# Joysticks_connection_unit.net
KiCad netlist of a schematic drawn in EAGLE
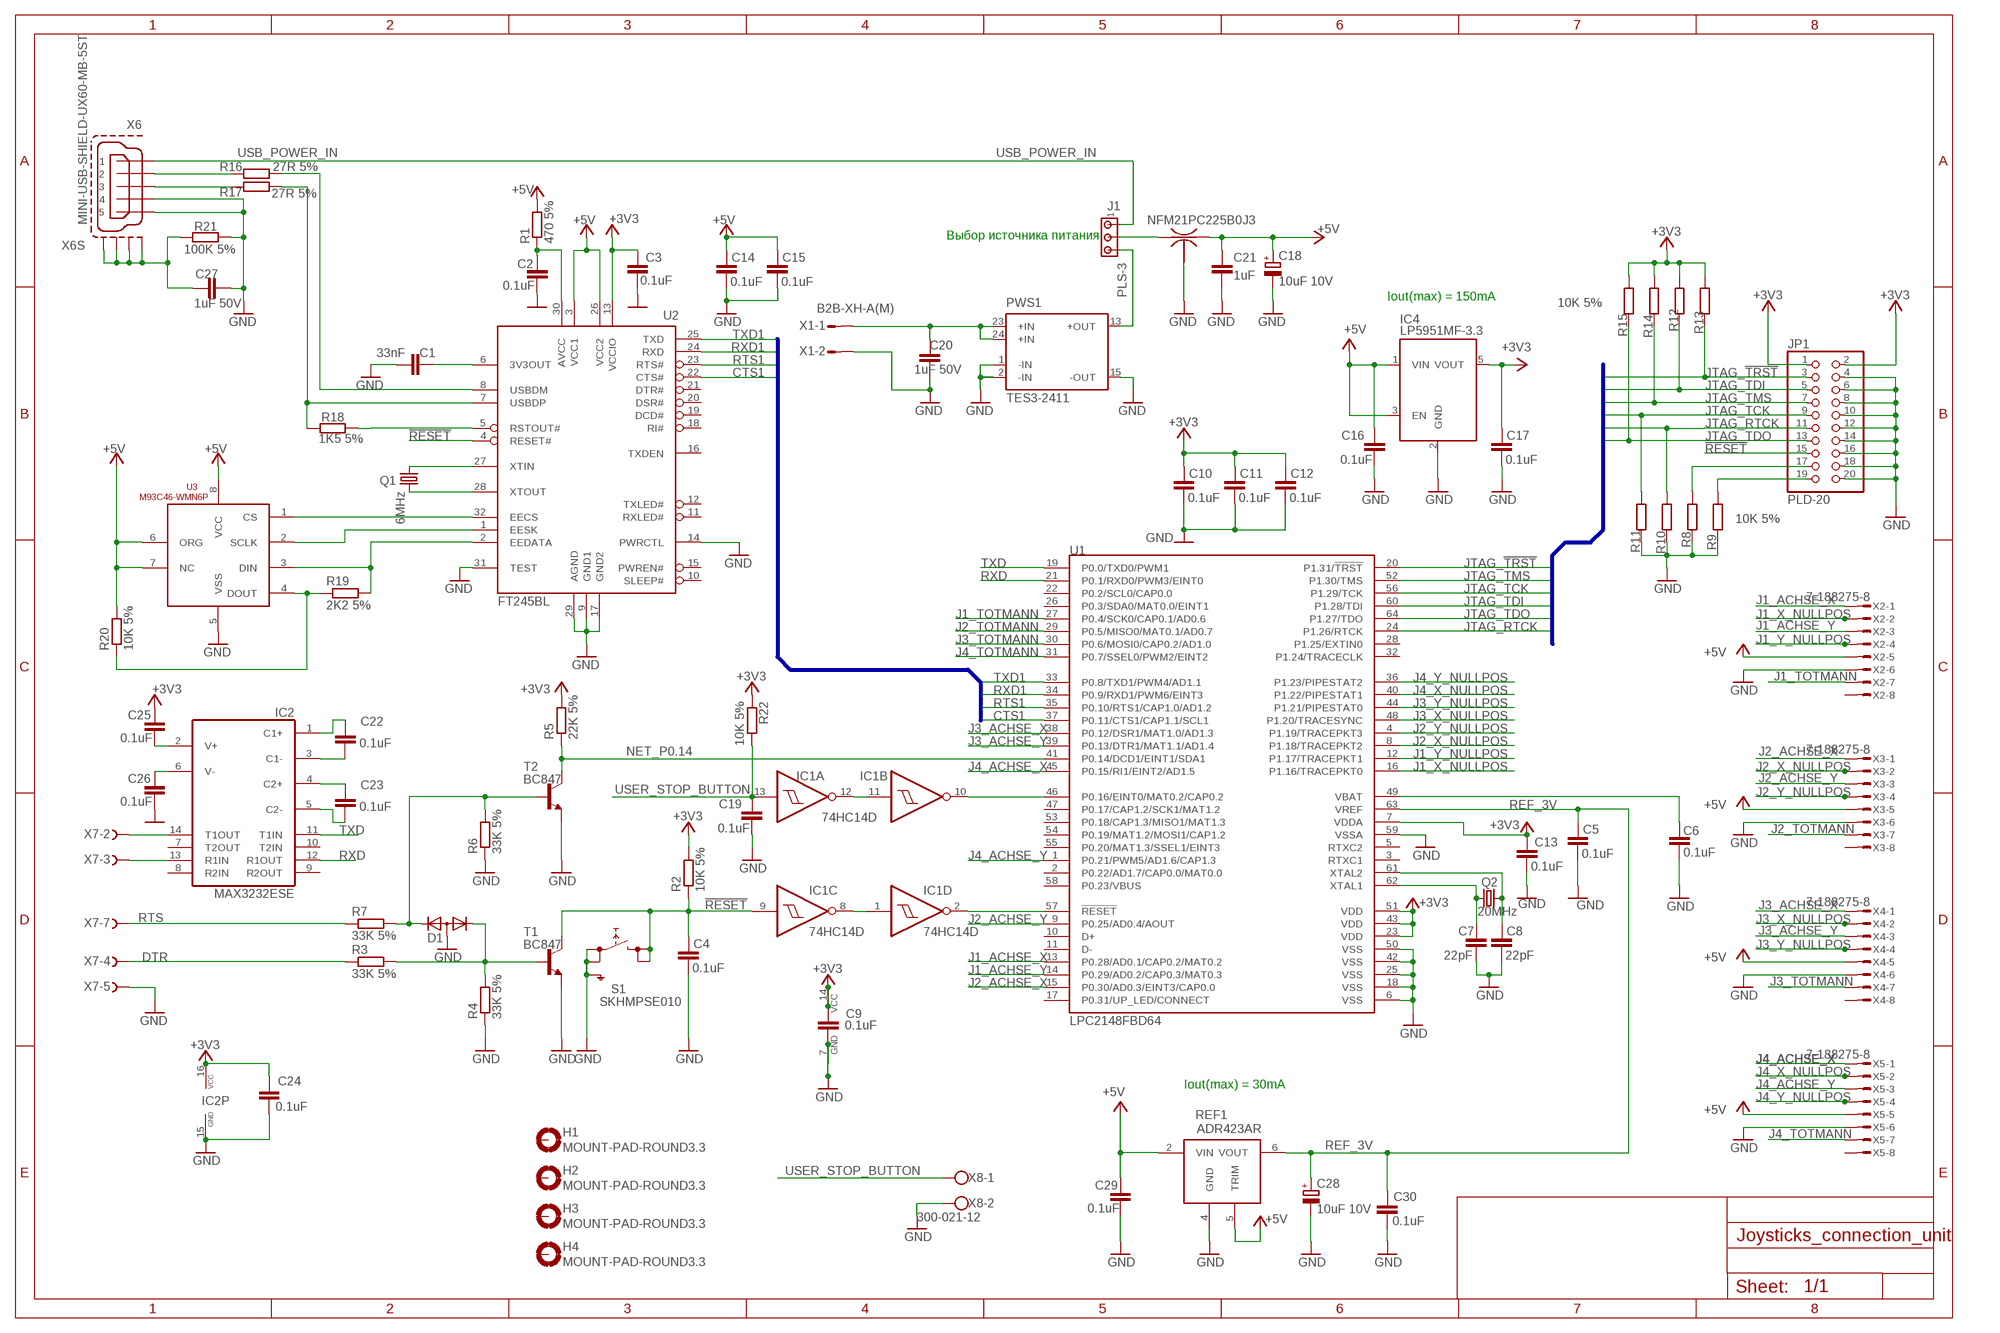
[diagram p0: schematic, sheet 1]

(export (version "E")
  (design (tool "Eeschema 10.0.6"))
  (components
    (comp (ref "C1")
      (value "33nF")
      (footprint "eagle-import:C0805")
      (libsource (lib "eagle-import") (part "C-EUC0805"))
    )
    (comp (ref "C2")
      (value "0.1uF")
      (footprint "eagle-import:C0805")
      (libsource (lib "eagle-import") (part "C-EUC0805"))
    )
    (comp (ref "C3")
      (value "0.1uF")
      (footprint "eagle-import:C0805")
      (libsource (lib "eagle-import") (part "C-EUC0805"))
    )
    (comp (ref "C4")
      (value "0.1uF")
      (footprint "eagle-import:C0805")
      (libsource (lib "eagle-import") (part "C-EUC0805"))
    )
    (comp (ref "C5")
      (value "0.1uF")
      (footprint "eagle-import:C0805")
      (libsource (lib "eagle-import") (part "C-EUC0805"))
    )
    (comp (ref "C6")
      (value "0.1uF")
      (footprint "eagle-import:C0805")
      (libsource (lib "eagle-import") (part "C-EUC0805"))
    )
    (comp (ref "C7")
      (value "22pF")
      (footprint "eagle-import:C0805")
      (libsource (lib "eagle-import") (part "C-EUC0805"))
    )
    (comp (ref "C8")
      (value "22pF")
      (footprint "eagle-import:C0805")
      (libsource (lib "eagle-import") (part "C-EUC0805"))
    )
    (comp (ref "C9")
      (value "0.1uF")
      (footprint "eagle-import:C0805")
      (libsource (lib "eagle-import") (part "C-EUC0805"))
    )
    (comp (ref "C10")
      (value "0.1uF")
      (footprint "eagle-import:C0805")
      (libsource (lib "eagle-import") (part "C-EUC0805"))
    )
    (comp (ref "C11")
      (value "0.1uF")
      (footprint "eagle-import:C0805")
      (libsource (lib "eagle-import") (part "C-EUC0805"))
    )
    (comp (ref "C12")
      (value "0.1uF")
      (footprint "eagle-import:C0805")
      (libsource (lib "eagle-import") (part "C-EUC0805"))
    )
    (comp (ref "C13")
      (value "0.1uF")
      (footprint "eagle-import:C0805")
      (libsource (lib "eagle-import") (part "C-EUC0805"))
    )
    (comp (ref "C14")
      (value "0.1uF")
      (footprint "eagle-import:C0805")
      (libsource (lib "eagle-import") (part "C-EUC0805"))
    )
    (comp (ref "C15")
      (value "0.1uF")
      (footprint "eagle-import:C0805")
      (libsource (lib "eagle-import") (part "C-EUC0805"))
    )
    (comp (ref "C16")
      (value "0.1uF")
      (footprint "eagle-import:C0805")
      (libsource (lib "eagle-import") (part "C-EUC0805"))
    )
    (comp (ref "C17")
      (value "0.1uF")
      (footprint "eagle-import:C0805")
      (libsource (lib "eagle-import") (part "C-EUC0805"))
    )
    (comp (ref "C18")
      (value "10uF 10V")
      (footprint "eagle-import:SMC_B")
      (libsource (lib "eagle-import") (part "CPOL-EUSMCB"))
    )
    (comp (ref "C19")
      (value "0.1uF")
      (footprint "eagle-import:C0805")
      (libsource (lib "eagle-import") (part "C-EUC0805"))
    )
    (comp (ref "C20")
      (value "1uF 50V")
      (footprint "eagle-import:C0805")
      (libsource (lib "eagle-import") (part "C-EUC0805"))
    )
    (comp (ref "C21")
      (value "1uF")
      (footprint "eagle-import:C0805")
      (libsource (lib "eagle-import") (part "C-EUC0805"))
    )
    (comp (ref "C22")
      (value "0.1uF")
      (footprint "eagle-import:C0805")
      (libsource (lib "eagle-import") (part "C-EUC0805"))
    )
    (comp (ref "C23")
      (value "0.1uF")
      (footprint "eagle-import:C0805")
      (libsource (lib "eagle-import") (part "C-EUC0805"))
    )
    (comp (ref "C24")
      (value "0.1uF")
      (footprint "eagle-import:C0805")
      (libsource (lib "eagle-import") (part "C-EUC0805"))
    )
    (comp (ref "C25")
      (value "0.1uF")
      (footprint "eagle-import:C0805")
      (libsource (lib "eagle-import") (part "C-EUC0805"))
    )
    (comp (ref "C26")
      (value "0.1uF")
      (footprint "eagle-import:C0805")
      (libsource (lib "eagle-import") (part "C-EUC0805"))
    )
    (comp (ref "C27")
      (value "1uF 50V")
      (footprint "eagle-import:C0805")
      (libsource (lib "eagle-import") (part "C-EUC0805"))
    )
    (comp (ref "C28")
      (value "10uF 10V")
      (footprint "eagle-import:SMC_B")
      (libsource (lib "eagle-import") (part "CPOL-EUSMCB"))
    )
    (comp (ref "C29")
      (value "0.1uF")
      (footprint "eagle-import:C0805")
      (libsource (lib "eagle-import") (part "C-EUC0805"))
    )
    (comp (ref "C30")
      (value "0.1uF")
      (footprint "eagle-import:C0805")
      (libsource (lib "eagle-import") (part "C-EUC0805"))
    )
    (comp (ref "CF1")
      (value "NFM21PC225B0J3")
      (footprint "eagle-import:NFM21C")
      (fields (field (name "MPN") "NFM21CC102R1H3D"))
      (libsource (lib "eagle-import") (part "NFM21C"))
    )
    (comp (ref "D1")
      (value "DIODE-2CA|ACSOT23")
      (footprint "eagle-import:SOT23")
      (libsource (lib "eagle-import") (part "DIODE-2CA|ACSOT23"))
    )
    (comp (ref "H1")
      (value "MOUNT-PAD-ROUND3.3")
      (footprint "eagle-import:3,3-PAD")
      (libsource (lib "eagle-import") (part "MOUNT-PAD-ROUND3.3"))
    )
    (comp (ref "H2")
      (value "MOUNT-PAD-ROUND3.3")
      (footprint "eagle-import:3,3-PAD")
      (libsource (lib "eagle-import") (part "MOUNT-PAD-ROUND3.3"))
    )
    (comp (ref "H3")
      (value "MOUNT-PAD-ROUND3.3")
      (footprint "eagle-import:3,3-PAD")
      (libsource (lib "eagle-import") (part "MOUNT-PAD-ROUND3.3"))
    )
    (comp (ref "H4")
      (value "MOUNT-PAD-ROUND3.3")
      (footprint "eagle-import:3,3-PAD")
      (libsource (lib "eagle-import") (part "MOUNT-PAD-ROUND3.3"))
    )
    (comp (ref "IC1")
      (value "74HC14D")
      (footprint "eagle-import:SO14")
      (libsource (lib "eagle-import") (part "7414DHC"))
    )
    (comp (ref "IC2")
      (value "MAX3232ESE")
      (footprint "eagle-import:SO16")
      (fields (field (name "MF") "MAXIM"))
      (libsource (lib "eagle-import") (part "MAX3232SEE"))
    )
    (comp (ref "IC4")
      (value "LP5951MF-3.3")
      (footprint "eagle-import:SOT23-5(MF05A)")
      (libsource (lib "eagle-import") (part "LP5951MF-3.3"))
    )
    (comp (ref "J1")
      (value "PLS-3")
      (footprint "eagle-import:10X03MTA")
      (libsource (lib "eagle-import") (part "MTA03-100"))
    )
    (comp (ref "JP1")
      (value "PLD-20")
      (footprint "eagle-import:2X10")
      (libsource (lib "eagle-import") (part "PINHD-2X10"))
    )
    (comp (ref "PWS1")
      (value "TES3-2411")
      (footprint "eagle-import:TES3")
      (libsource (lib "eagle-import") (part "TES3-2411"))
    )
    (comp (ref "Q1")
      (value "6MHz")
      (footprint "eagle-import:HC49_S")
      (fields (field (name "OC_FARNELL") "1667008") (field (name "OC_NEWARK") "unknown"))
      (libsource (lib "eagle-import") (part "CRYSTALHC49S"))
    )
    (comp (ref "Q2")
      (value "20MHz")
      (footprint "eagle-import:HC49_S")
      (libsource (lib "eagle-import") (part "CRYSTALHC49S"))
    )
    (comp (ref "R1")
      (value "470 5%")
      (footprint "eagle-import:R0805")
      (libsource (lib "eagle-import") (part "R-EU_R0805"))
    )
    (comp (ref "R2")
      (value "10K 5%")
      (footprint "eagle-import:R0805")
      (libsource (lib "eagle-import") (part "R-EU_R0805"))
    )
    (comp (ref "R3")
      (value "33K 5%")
      (footprint "eagle-import:R0805")
      (libsource (lib "eagle-import") (part "R-EU_R0805"))
    )
    (comp (ref "R4")
      (value "33K 5%")
      (footprint "eagle-import:R0805")
      (libsource (lib "eagle-import") (part "R-EU_R0805"))
    )
    (comp (ref "R5")
      (value "22K 5%")
      (footprint "eagle-import:R0805")
      (libsource (lib "eagle-import") (part "R-EU_R0805"))
    )
    (comp (ref "R6")
      (value "33K 5%")
      (footprint "eagle-import:R0805")
      (libsource (lib "eagle-import") (part "R-EU_R0805"))
    )
    (comp (ref "R7")
      (value "33K 5%")
      (footprint "eagle-import:R0805")
      (libsource (lib "eagle-import") (part "R-EU_R0805"))
    )
    (comp (ref "R8")
      (value "10K 5%")
      (footprint "eagle-import:R0805")
      (libsource (lib "eagle-import") (part "R-EU_R0805"))
    )
    (comp (ref "R9")
      (value "10K 5%")
      (footprint "eagle-import:R0805")
      (libsource (lib "eagle-import") (part "R-EU_R0805"))
    )
    (comp (ref "R10")
      (value "10K 5%")
      (footprint "eagle-import:R0805")
      (libsource (lib "eagle-import") (part "R-EU_R0805"))
    )
    (comp (ref "R11")
      (value "10K 5%")
      (footprint "eagle-import:R0805")
      (libsource (lib "eagle-import") (part "R-EU_R0805"))
    )
    (comp (ref "R12")
      (value "10K 5%")
      (footprint "eagle-import:R0805")
      (libsource (lib "eagle-import") (part "R-EU_R0805"))
    )
    (comp (ref "R13")
      (value "10K 5%")
      (footprint "eagle-import:R0805")
      (libsource (lib "eagle-import") (part "R-EU_R0805"))
    )
    (comp (ref "R14")
      (value "10K 5%")
      (footprint "eagle-import:R0805")
      (libsource (lib "eagle-import") (part "R-EU_R0805"))
    )
    (comp (ref "R15")
      (value "10K 5%")
      (footprint "eagle-import:R0805")
      (libsource (lib "eagle-import") (part "R-EU_R0805"))
    )
    (comp (ref "R16")
      (value "27R 5%")
      (footprint "eagle-import:R0805")
      (libsource (lib "eagle-import") (part "R-EU_R0805"))
    )
    (comp (ref "R17")
      (value "27R 5%")
      (footprint "eagle-import:R0805")
      (libsource (lib "eagle-import") (part "R-EU_R0805"))
    )
    (comp (ref "R18")
      (value "1K5 5%")
      (footprint "eagle-import:R0805")
      (libsource (lib "eagle-import") (part "R-EU_R0805"))
    )
    (comp (ref "R19")
      (value "2K2 5%")
      (footprint "eagle-import:R0805")
      (libsource (lib "eagle-import") (part "R-EU_R0805"))
    )
    (comp (ref "R20")
      (value "10K 5%")
      (footprint "eagle-import:R0805")
      (libsource (lib "eagle-import") (part "R-EU_R0805"))
    )
    (comp (ref "R21")
      (value "100K 5%")
      (footprint "eagle-import:R0805")
      (libsource (lib "eagle-import") (part "R-EU_R0805"))
    )
    (comp (ref "R22")
      (value "10K 5%")
      (footprint "eagle-import:R0805")
      (libsource (lib "eagle-import") (part "R-EU_R0805"))
    )
    (comp (ref "REF1")
      (value "ADR423AR")
      (footprint "eagle-import:SOIC8")
      (libsource (lib "eagle-import") (part "ADR423AR"))
    )
    (comp (ref "S1")
      (value "SKHMPSE010")
      (footprint "eagle-import:SKHMPXE010")
      (libsource (lib "eagle-import") (part "SKHMPE010S"))
    )
    (comp (ref "T1")
      (value "BC847")
      (footprint "eagle-import:SOT23")
      (libsource (lib "eagle-import") (part "BC847"))
    )
    (comp (ref "T2")
      (value "BC847")
      (footprint "eagle-import:SOT23")
      (libsource (lib "eagle-import") (part "BC847"))
    )
    (comp (ref "U1")
      (value "LPC2148FBD64")
      (footprint "eagle-import:TSQFP50P1200X1200X160-64N")
      (libsource (lib "eagle-import") (part "LPC2148FBD64"))
    )
    (comp (ref "U2")
      (value "FT245BL")
      (footprint "eagle-import:LQFP32")
      (libsource (lib "eagle-import") (part "FT245BL"))
    )
    (comp (ref "U3")
      (value "M93C46-WMN6P")
      (footprint "eagle-import:SO8")
      (libsource (lib "eagle-import") (part "M93C46-WMN6P"))
    )
    (comp (ref "X1")
      (value "B2B-XH-A(M)")
      (footprint "eagle-import:B2B-XH-AM")
      (libsource (lib "eagle-import") (part "B2B-XH-A(M)"))
    )
    (comp (ref "X2")
      (value "7-188275-8")
      (footprint "eagle-import:MMT-F-SMD-8")
      (libsource (lib "eagle-import") (part "MICROMATCH-8SMF"))
    )
    (comp (ref "X3")
      (value "7-188275-8")
      (footprint "eagle-import:MMT-F-SMD-8")
      (libsource (lib "eagle-import") (part "MICROMATCH-8SMF"))
    )
    (comp (ref "X4")
      (value "7-188275-8")
      (footprint "eagle-import:MMT-F-SMD-8")
      (libsource (lib "eagle-import") (part "MICROMATCH-8SMF"))
    )
    (comp (ref "X5")
      (value "7-188275-8")
      (footprint "eagle-import:MMT-F-SMD-8")
      (libsource (lib "eagle-import") (part "MICROMATCH-8SMF"))
    )
    (comp (ref "X6")
      (value "MINI-USB-SHIELD-UX60-MB-5ST")
      (footprint "eagle-import:UX60-MB-5ST")
      (libsource (lib "eagle-import") (part "MINI-USB-SHIELD-UX60-MB-5ST"))
    )
    (comp (ref "X7")
      (value "F09VPS")
      (footprint "eagle-import:F09VP")
      (libsource (lib "eagle-import") (part "F09?SVP"))
    )
    (comp (ref "X8")
      (value "300-021-12")
      (footprint "eagle-import:W237-102")
      (fields (field (name "MPN") "237-102"))
      (libsource (lib "eagle-import") (part "W237-102"))
    )
  )
  (nets
    (net (code "1") (name "+3V3") (class "Default")
      (node (ref "C10") (pin "1") (pinfunction "1_1") (pintype "passive"))
      (node (ref "C11") (pin "1") (pinfunction "1_1") (pintype "passive"))
      (node (ref "C12") (pin "1") (pinfunction "1_1") (pintype "passive"))
      (node (ref "C13") (pin "1") (pinfunction "1_1") (pintype "passive"))
      (node (ref "C17") (pin "1") (pinfunction "1_1") (pintype "passive"))
      (node (ref "C24") (pin "1") (pinfunction "1_1") (pintype "passive"))
      (node (ref "C25") (pin "1") (pinfunction "1_1") (pintype "passive"))
      (node (ref "C3") (pin "1") (pinfunction "1_1") (pintype "passive"))
      (node (ref "C9") (pin "1") (pinfunction "1_1") (pintype "passive"))
      (node (ref "IC1") (pin "14") (pinfunction "VCC_14") (pintype "power_in"))
      (node (ref "IC2") (pin "16") (pinfunction "VCC_16") (pintype "power_in"))
      (node (ref "IC4") (pin "5") (pinfunction "VOUT_5") (pintype "power_in"))
      (node (ref "JP1") (pin "1") (pinfunction "1_1") (pintype "passive"))
      (node (ref "JP1") (pin "2") (pinfunction "2_2") (pintype "passive"))
      (node (ref "R12") (pin "2") (pinfunction "2_2") (pintype "passive"))
      (node (ref "R13") (pin "2") (pinfunction "2_2") (pintype "passive"))
      (node (ref "R14") (pin "2") (pinfunction "2_2") (pintype "passive"))
      (node (ref "R15") (pin "2") (pinfunction "2_2") (pintype "passive"))
      (node (ref "R2") (pin "2") (pinfunction "2_2") (pintype "passive"))
      (node (ref "R22") (pin "1") (pinfunction "1_1") (pintype "passive"))
      (node (ref "R5") (pin "2") (pinfunction "2_2") (pintype "passive"))
      (node (ref "U1") (pin "23") (pinfunction "VDD_23") (pintype "power_in"))
      (node (ref "U1") (pin "43") (pinfunction "VDD_43") (pintype "power_in"))
      (node (ref "U1") (pin "51") (pinfunction "VDD_51") (pintype "power_in"))
      (node (ref "U1") (pin "7") (pinfunction "VDDA_7") (pintype "power_in"))
      (node (ref "U2") (pin "13") (pinfunction "VCCIO_13") (pintype "power_in"))
    )
    (net (code "2") (name "+5V") (class "Default")
      (node (ref "C14") (pin "1") (pinfunction "1_1") (pintype "passive"))
      (node (ref "C15") (pin "1") (pinfunction "1_1") (pintype "passive"))
      (node (ref "C16") (pin "1") (pinfunction "1_1") (pintype "passive"))
      (node (ref "C18") (pin "+") (pinfunction "+_+") (pintype "passive"))
      (node (ref "C21") (pin "1") (pinfunction "1_1") (pintype "passive"))
      (node (ref "C29") (pin "1") (pinfunction "1_1") (pintype "passive"))
      (node (ref "CF1") (pin "3") (pinfunction "3_3") (pintype "passive"))
      (node (ref "IC4") (pin "1") (pinfunction "VIN_1") (pintype "input"))
      (node (ref "IC4") (pin "3") (pinfunction "EN_3") (pintype "input"))
      (node (ref "R1") (pin "2") (pinfunction "2_2") (pintype "passive"))
      (node (ref "R20") (pin "2") (pinfunction "2_2") (pintype "passive"))
      (node (ref "REF1") (pin "2") (pinfunction "VIN_2") (pintype "input"))
      (node (ref "REF1") (pin "5") (pinfunction "TRIM_5") (pintype "input"))
      (node (ref "U2") (pin "26") (pinfunction "VCC2_26") (pintype "power_in"))
      (node (ref "U2") (pin "3") (pinfunction "VCC1_3") (pintype "power_in"))
      (node (ref "U3") (pin "6") (pinfunction "ORG_6") (pintype "input"))
      (node (ref "U3") (pin "7") (pinfunction "NC_7") (pintype "input"))
      (node (ref "U3") (pin "8") (pinfunction "VCC_8") (pintype "power_in"))
      (node (ref "X2") (pin "5") (pinfunction "S_5") (pintype "passive"))
      (node (ref "X3") (pin "5") (pinfunction "S_5") (pintype "passive"))
      (node (ref "X4") (pin "5") (pinfunction "S_5") (pintype "passive"))
      (node (ref "X5") (pin "5") (pinfunction "S_5") (pintype "passive"))
    )
    (net (code "3") (name "/CTS1") (class "Default")
      (node (ref "U1") (pin "37") (pinfunction "P0.11/CTS1/CAP1.1/SCL1_37") (pintype "bidirectional"))
      (node (ref "U2") (pin "22") (pinfunction "CTS#_22") (pintype "input"))
    )
    (net (code "4") (name "/DTR") (class "Default")
      (node (ref "R3") (pin "1") (pinfunction "1_1") (pintype "passive"))
      (node (ref "X7") (pin "4") (pinfunction "F_4") (pintype "passive"))
    )
    (net (code "5") (name "/J1_ACHSE_X") (class "Default")
      (node (ref "U1") (pin "13") (pinfunction "P0.28/AD0.1/CAP0.2/MAT0.2_13") (pintype "bidirectional"))
      (node (ref "X2") (pin "1") (pinfunction "S_1") (pintype "passive"))
    )
    (net (code "6") (name "/J1_ACHSE_Y") (class "Default")
      (node (ref "U1") (pin "14") (pinfunction "P0.29/AD0.2/CAP0.3/MAT0.3_14") (pintype "bidirectional"))
      (node (ref "X2") (pin "3") (pinfunction "S_3") (pintype "passive"))
    )
    (net (code "7") (name "/J1_TOTMANN") (class "Default")
      (node (ref "U1") (pin "27") (pinfunction "P0.4/SCK0/CAP0.1/AD0.6_27") (pintype "bidirectional"))
      (node (ref "X2") (pin "7") (pinfunction "S_7") (pintype "passive"))
    )
    (net (code "8") (name "/J1_X_NULLPOS") (class "Default")
      (node (ref "U1") (pin "16") (pinfunction "P1.16/TRACEPKT0_16") (pintype "bidirectional"))
      (node (ref "X2") (pin "2") (pinfunction "S_2") (pintype "passive"))
    )
    (net (code "9") (name "/J1_Y_NULLPOS") (class "Default")
      (node (ref "U1") (pin "12") (pinfunction "P1.17/TRACEPKT1_12") (pintype "bidirectional"))
      (node (ref "X2") (pin "4") (pinfunction "S_4") (pintype "passive"))
    )
    (net (code "10") (name "/J2_ACHSE_X") (class "Default")
      (node (ref "U1") (pin "15") (pinfunction "P0.30/AD0.3/EINT3/CAP0.0_15") (pintype "bidirectional"))
      (node (ref "X3") (pin "1") (pinfunction "S_1") (pintype "passive"))
    )
    (net (code "11") (name "/J2_ACHSE_Y") (class "Default")
      (node (ref "U1") (pin "9") (pinfunction "P0.25/AD0.4/AOUT_9") (pintype "bidirectional"))
      (node (ref "X3") (pin "3") (pinfunction "S_3") (pintype "passive"))
    )
    (net (code "12") (name "/J2_TOTMANN") (class "Default")
      (node (ref "U1") (pin "29") (pinfunction "P0.5/MISO0/MAT0.1/AD0.7_29") (pintype "bidirectional"))
      (node (ref "X3") (pin "7") (pinfunction "S_7") (pintype "passive"))
    )
    (net (code "13") (name "/J2_X_NULLPOS") (class "Default")
      (node (ref "U1") (pin "8") (pinfunction "P1.18/TRACEPKT2_8") (pintype "bidirectional"))
      (node (ref "X3") (pin "2") (pinfunction "S_2") (pintype "passive"))
    )
    (net (code "14") (name "/J2_Y_NULLPOS") (class "Default")
      (node (ref "U1") (pin "4") (pinfunction "P1.19/TRACEPKT3_4") (pintype "bidirectional"))
      (node (ref "X3") (pin "4") (pinfunction "S_4") (pintype "passive"))
    )
    (net (code "15") (name "/J3_ACHSE_X") (class "Default")
      (node (ref "U1") (pin "38") (pinfunction "P0.12/DSR1/MAT1.0/AD1.3_38") (pintype "bidirectional"))
      (node (ref "X4") (pin "1") (pinfunction "S_1") (pintype "passive"))
    )
    (net (code "16") (name "/J3_ACHSE_Y") (class "Default")
      (node (ref "U1") (pin "39") (pinfunction "P0.13/DTR1/MAT1.1/AD1.4_39") (pintype "bidirectional"))
      (node (ref "X4") (pin "3") (pinfunction "S_3") (pintype "passive"))
    )
    (net (code "17") (name "/J3_TOTMANN") (class "Default")
      (node (ref "U1") (pin "30") (pinfunction "P0.6/MOSI0/CAP0.2/AD1.0_30") (pintype "bidirectional"))
      (node (ref "X4") (pin "7") (pinfunction "S_7") (pintype "passive"))
    )
    (net (code "18") (name "/J3_X_NULLPOS") (class "Default")
      (node (ref "U1") (pin "48") (pinfunction "P1.20/TRACESYNC_48") (pintype "bidirectional"))
      (node (ref "X4") (pin "2") (pinfunction "S_2") (pintype "passive"))
    )
    (net (code "19") (name "/J3_Y_NULLPOS") (class "Default")
      (node (ref "U1") (pin "44") (pinfunction "P1.21/PIPESTAT0_44") (pintype "bidirectional"))
      (node (ref "X4") (pin "4") (pinfunction "S_4") (pintype "passive"))
    )
    (net (code "20") (name "/J4_ACHSE_X") (class "Default")
      (node (ref "U1") (pin "45") (pinfunction "P0.15/RI1/EINT2/AD1.5_45") (pintype "bidirectional"))
      (node (ref "X5") (pin "1") (pinfunction "S_1") (pintype "passive"))
    )
    (net (code "21") (name "/J4_ACHSE_Y") (class "Default")
      (node (ref "U1") (pin "1") (pinfunction "P0.21/PWM5/AD1.6/CAP1.3_1") (pintype "bidirectional"))
      (node (ref "X5") (pin "3") (pinfunction "S_3") (pintype "passive"))
    )
    (net (code "22") (name "/J4_TOTMANN") (class "Default")
      (node (ref "U1") (pin "31") (pinfunction "P0.7/SSEL0/PWM2/EINT2_31") (pintype "bidirectional"))
      (node (ref "X5") (pin "7") (pinfunction "S_7") (pintype "passive"))
    )
    (net (code "23") (name "/J4_X_NULLPOS") (class "Default")
      (node (ref "U1") (pin "40") (pinfunction "P1.22/PIPESTAT1_40") (pintype "bidirectional"))
      (node (ref "X5") (pin "2") (pinfunction "S_2") (pintype "passive"))
    )
    (net (code "24") (name "/J4_Y_NULLPOS") (class "Default")
      (node (ref "U1") (pin "36") (pinfunction "P1.23/PIPESTAT2_36") (pintype "bidirectional"))
      (node (ref "X5") (pin "4") (pinfunction "S_4") (pintype "passive"))
    )
    (net (code "25") (name "/JTAG_RTCK") (class "Default")
      (node (ref "JP1") (pin "11") (pinfunction "11_11") (pintype "passive"))
      (node (ref "R10") (pin "2") (pinfunction "2_2") (pintype "passive"))
      (node (ref "U1") (pin "24") (pinfunction "P1.26/RTCK_24") (pintype "bidirectional"))
    )
    (net (code "26") (name "/JTAG_TCK") (class "Default")
      (node (ref "JP1") (pin "9") (pinfunction "9_9") (pintype "passive"))
      (node (ref "R11") (pin "2") (pinfunction "2_2") (pintype "passive"))
      (node (ref "U1") (pin "56") (pinfunction "P1.29/TCK_56") (pintype "bidirectional"))
    )
    (net (code "27") (name "/JTAG_TDI") (class "Default")
      (node (ref "JP1") (pin "5") (pinfunction "5_5") (pintype "passive"))
      (node (ref "R12") (pin "1") (pinfunction "1_1") (pintype "passive"))
      (node (ref "U1") (pin "60") (pinfunction "P1.28/TDI_60") (pintype "bidirectional"))
    )
    (net (code "28") (name "/JTAG_TDO") (class "Default")
      (node (ref "JP1") (pin "13") (pinfunction "13_13") (pintype "passive"))
      (node (ref "R15") (pin "1") (pinfunction "1_1") (pintype "passive"))
      (node (ref "U1") (pin "64") (pinfunction "P1.27/TDO_64") (pintype "bidirectional"))
    )
    (net (code "29") (name "/JTAG_TMS") (class "Default")
      (node (ref "JP1") (pin "7") (pinfunction "7_7") (pintype "passive"))
      (node (ref "R14") (pin "1") (pinfunction "1_1") (pintype "passive"))
      (node (ref "U1") (pin "52") (pinfunction "P1.30/TMS_52") (pintype "bidirectional"))
    )
    (net (code "30") (name "/JTAG_~{TRST}") (class "Default")
      (node (ref "JP1") (pin "3") (pinfunction "3_3") (pintype "passive"))
      (node (ref "R13") (pin "1") (pinfunction "1_1") (pintype "passive"))
      (node (ref "U1") (pin "20") (pinfunction "P1.31/~{TRST}_20") (pintype "bidirectional"))
    )
    (net (code "31") (name "/NET_P0.14") (class "Default")
      (node (ref "R5") (pin "1") (pinfunction "1_1") (pintype "passive"))
      (node (ref "T2") (pin "3") (pinfunction "C_3") (pintype "passive"))
      (node (ref "U1") (pin "41") (pinfunction "P0.14/DCD1/EINT1/SDA1_41") (pintype "bidirectional"))
    )
    (net (code "32") (name "/REF_3V") (class "Default")
      (node (ref "C28") (pin "+") (pinfunction "+_+") (pintype "passive"))
      (node (ref "C30") (pin "1") (pinfunction "1_1") (pintype "passive"))
      (node (ref "C5") (pin "1") (pinfunction "1_1") (pintype "passive"))
      (node (ref "REF1") (pin "6") (pinfunction "VOUT_6") (pintype "output"))
      (node (ref "U1") (pin "63") (pinfunction "VREF_63") (pintype "input"))
    )
    (net (code "33") (name "/RTS") (class "Default")
      (node (ref "R7") (pin "1") (pinfunction "1_1") (pintype "passive"))
      (node (ref "X7") (pin "7") (pinfunction "F_7") (pintype "passive"))
    )
    (net (code "34") (name "/RTS1") (class "Default")
      (node (ref "U1") (pin "35") (pinfunction "P0.10/RTS1/CAP1.0/AD1.2_35") (pintype "bidirectional"))
      (node (ref "U2") (pin "23") (pinfunction "RTS#_23") (pintype "output"))
    )
    (net (code "35") (name "/RXD") (class "Default")
      (node (ref "IC2") (pin "12") (pinfunction "R1OUT_12") (pintype "output"))
      (node (ref "U1") (pin "21") (pinfunction "P0.1/RXD0/PWM3/EINT0_21") (pintype "bidirectional"))
    )
    (net (code "36") (name "/RXD1") (class "Default")
      (node (ref "U1") (pin "34") (pinfunction "P0.9/RXD1/PWM6/EINT3_34") (pintype "bidirectional"))
      (node (ref "U2") (pin "24") (pinfunction "RXD_24") (pintype "input"))
    )
    (net (code "37") (name "/TXD") (class "Default")
      (node (ref "IC2") (pin "11") (pinfunction "T1IN_11") (pintype "input"))
      (node (ref "U1") (pin "19") (pinfunction "P0.0/TXD0/PWM1_19") (pintype "bidirectional"))
    )
    (net (code "38") (name "/TXD1") (class "Default")
      (node (ref "U1") (pin "33") (pinfunction "P0.8/TXD1/PWM4/AD1.1_33") (pintype "bidirectional"))
      (node (ref "U2") (pin "25") (pinfunction "TXD_25") (pintype "output"))
    )
    (net (code "39") (name "/USB_POWER_IN") (class "Default")
      (node (ref "J1") (pin "1") (pinfunction "1_1") (pintype "passive"))
      (node (ref "X6") (pin "1") (pinfunction "1_1") (pintype "input"))
    )
    (net (code "40") (name "/USER_STOP_BUTTON") (class "Default")
      (node (ref "C19") (pin "1") (pinfunction "1_1") (pintype "passive"))
      (node (ref "IC1") (pin "13") (pinfunction "I_13") (pintype "input"))
      (node (ref "R22") (pin "2") (pinfunction "2_2") (pintype "passive"))
      (node (ref "X8") (pin "1") (pinfunction "KL_1") (pintype "passive"))
    )
    (net (code "41") (name "/~{RESET}") (class "Default")
      (node (ref "C4") (pin "1") (pinfunction "1_1") (pintype "passive"))
      (node (ref "IC1") (pin "9") (pinfunction "I_9") (pintype "input"))
      (node (ref "JP1") (pin "15") (pinfunction "15_15") (pintype "passive"))
      (node (ref "R2") (pin "1") (pinfunction "1_1") (pintype "passive"))
      (node (ref "S1") (pin "3") (pinfunction "2.1_3") (pintype "passive"))
      (node (ref "S1") (pin "4") (pinfunction "2.2_4") (pintype "passive"))
      (node (ref "T1") (pin "3") (pinfunction "C_3") (pintype "passive"))
      (node (ref "U2") (pin "4") (pinfunction "RESET#_4") (pintype "input"))
    )
    (net (code "42") (name "GND") (class "Default")
      (node (ref "C1") (pin "2") (pinfunction "2_2") (pintype "passive"))
      (node (ref "C10") (pin "2") (pinfunction "2_2") (pintype "passive"))
      (node (ref "C11") (pin "2") (pinfunction "2_2") (pintype "passive"))
      (node (ref "C12") (pin "2") (pinfunction "2_2") (pintype "passive"))
      (node (ref "C13") (pin "2") (pinfunction "2_2") (pintype "passive"))
      (node (ref "C14") (pin "2") (pinfunction "2_2") (pintype "passive"))
      (node (ref "C15") (pin "2") (pinfunction "2_2") (pintype "passive"))
      (node (ref "C16") (pin "2") (pinfunction "2_2") (pintype "passive"))
      (node (ref "C17") (pin "2") (pinfunction "2_2") (pintype "passive"))
      (node (ref "C18") (pin "-") (pinfunction "-_-") (pintype "passive"))
      (node (ref "C19") (pin "2") (pinfunction "2_2") (pintype "passive"))
      (node (ref "C2") (pin "2") (pinfunction "2_2") (pintype "passive"))
      (node (ref "C20") (pin "2") (pinfunction "2_2") (pintype "passive"))
      (node (ref "C21") (pin "2") (pinfunction "2_2") (pintype "passive"))
      (node (ref "C24") (pin "2") (pinfunction "2_2") (pintype "passive"))
      (node (ref "C26") (pin "2") (pinfunction "2_2") (pintype "passive"))
      (node (ref "C27") (pin "2") (pinfunction "2_2") (pintype "passive"))
      (node (ref "C28") (pin "-") (pinfunction "-_-") (pintype "passive"))
      (node (ref "C29") (pin "2") (pinfunction "2_2") (pintype "passive"))
      (node (ref "C3") (pin "2") (pinfunction "2_2") (pintype "passive"))
      (node (ref "C30") (pin "2") (pinfunction "2_2") (pintype "passive"))
      (node (ref "C4") (pin "2") (pinfunction "2_2") (pintype "passive"))
      (node (ref "C5") (pin "2") (pinfunction "2_2") (pintype "passive"))
      (node (ref "C6") (pin "2") (pinfunction "2_2") (pintype "passive"))
      (node (ref "C7") (pin "2") (pinfunction "2_2") (pintype "passive"))
      (node (ref "C8") (pin "2") (pinfunction "2_2") (pintype "passive"))
      (node (ref "C9") (pin "2") (pinfunction "2_2") (pintype "passive"))
      (node (ref "CF1") (pin "2@1") (pinfunction "2_2@1") (pintype "passive"))
      (node (ref "D1") (pin "3") (pinfunction "A_3") (pintype "passive"))
      (node (ref "IC1") (pin "7") (pinfunction "GND_7") (pintype "power_in"))
      (node (ref "IC2") (pin "15") (pinfunction "GND_15") (pintype "power_in"))
      (node (ref "IC4") (pin "2") (pinfunction "GND_2") (pintype "power_in"))
      (node (ref "JP1") (pin "10") (pinfunction "10_10") (pintype "passive"))
      (node (ref "JP1") (pin "12") (pinfunction "12_12") (pintype "passive"))
      (node (ref "JP1") (pin "14") (pinfunction "14_14") (pintype "passive"))
      (node (ref "JP1") (pin "16") (pinfunction "16_16") (pintype "passive"))
      (node (ref "JP1") (pin "18") (pinfunction "18_18") (pintype "passive"))
      (node (ref "JP1") (pin "20") (pinfunction "20_20") (pintype "passive"))
      (node (ref "JP1") (pin "4") (pinfunction "4_4") (pintype "passive"))
      (node (ref "JP1") (pin "6") (pinfunction "6_6") (pintype "passive"))
      (node (ref "JP1") (pin "8") (pinfunction "8_8") (pintype "passive"))
      (node (ref "PWS1") (pin "1") (pinfunction "-IN_1") (pintype "input"))
      (node (ref "PWS1") (pin "15") (pinfunction "-OUT_15") (pintype "output"))
      (node (ref "PWS1") (pin "2") (pinfunction "-IN_2") (pintype "input"))
      (node (ref "R10") (pin "1") (pinfunction "1_1") (pintype "passive"))
      (node (ref "R11") (pin "1") (pinfunction "1_1") (pintype "passive"))
      (node (ref "R21") (pin "2") (pinfunction "2_2") (pintype "passive"))
      (node (ref "R4") (pin "1") (pinfunction "1_1") (pintype "passive"))
      (node (ref "R6") (pin "1") (pinfunction "1_1") (pintype "passive"))
      (node (ref "R8") (pin "1") (pinfunction "1_1") (pintype "passive"))
      (node (ref "R9") (pin "1") (pinfunction "1_1") (pintype "passive"))
      (node (ref "REF1") (pin "4") (pinfunction "GND_4") (pintype "power_in"))
      (node (ref "S1") (pin "1") (pinfunction "1.1_1") (pintype "passive"))
      (node (ref "S1") (pin "2") (pinfunction "1.2_2") (pintype "passive"))
      (node (ref "S1") (pin "5") (pinfunction "SH_5") (pintype "passive"))
      (node (ref "T1") (pin "2") (pinfunction "E_2") (pintype "passive"))
      (node (ref "T2") (pin "2") (pinfunction "E_2") (pintype "passive"))
      (node (ref "U1") (pin "18") (pinfunction "VSS_18") (pintype "power_in"))
      (node (ref "U1") (pin "25") (pinfunction "VSS_25") (pintype "power_in"))
      (node (ref "U1") (pin "42") (pinfunction "VSS_42") (pintype "power_in"))
      (node (ref "U1") (pin "50") (pinfunction "VSS_50") (pintype "power_in"))
      (node (ref "U1") (pin "59") (pinfunction "VSSA_59") (pintype "power_in"))
      (node (ref "U1") (pin "6") (pinfunction "VSS_6") (pintype "power_in"))
      (node (ref "U2") (pin "14") (pinfunction "PWRCTL_14") (pintype "input"))
      (node (ref "U2") (pin "17") (pinfunction "GND2_17") (pintype "power_in"))
      (node (ref "U2") (pin "29") (pinfunction "AGND_29") (pintype "power_in"))
      (node (ref "U2") (pin "31") (pinfunction "TEST_31") (pintype "input"))
      (node (ref "U2") (pin "9") (pinfunction "GND1_9") (pintype "power_in"))
      (node (ref "U3") (pin "5") (pinfunction "VSS_5") (pintype "power_in"))
      (node (ref "X1") (pin "2") (pinfunction "S_2") (pintype "passive"))
      (node (ref "X2") (pin "6") (pinfunction "S_6") (pintype "passive"))
      (node (ref "X3") (pin "6") (pinfunction "S_6") (pintype "passive"))
      (node (ref "X4") (pin "6") (pinfunction "S_6") (pintype "passive"))
      (node (ref "X5") (pin "6") (pinfunction "S_6") (pintype "passive"))
      (node (ref "X6") (pin "4") (pinfunction "4_4") (pintype "input"))
      (node (ref "X6") (pin "5") (pinfunction "5_5") (pintype "input"))
      (node (ref "X7") (pin "5") (pinfunction "F_5") (pintype "passive"))
      (node (ref "X8") (pin "2") (pinfunction "KL_2") (pintype "passive"))
    )
    (net (code "43") (name "Net-(CF1-Pad1)") (class "Default")
      (node (ref "CF1") (pin "1") (pinfunction "1_1") (pintype "passive"))
      (node (ref "J1") (pin "2") (pinfunction "2_2") (pintype "passive"))
    )
    (net (code "44") (name "Net-(D1-K1)") (class "Default")
      (node (ref "D1") (pin "1") (pinfunction "K1_1") (pintype "passive"))
      (node (ref "R3") (pin "2") (pinfunction "2_2") (pintype "passive"))
      (node (ref "R4") (pin "2") (pinfunction "2_2") (pintype "passive"))
      (node (ref "T1") (pin "1") (pinfunction "B_1") (pintype "passive"))
    )
    (net (code "45") (name "Net-(D1-K2)") (class "Default")
      (node (ref "D1") (pin "2") (pinfunction "K2_2") (pintype "passive"))
      (node (ref "R6") (pin "2") (pinfunction "2_2") (pintype "passive"))
      (node (ref "R7") (pin "2") (pinfunction "2_2") (pintype "passive"))
      (node (ref "T2") (pin "1") (pinfunction "B_1") (pintype "passive"))
    )
    (net (code "46") (name "Net-(IC1A-O)") (class "Default")
      (node (ref "IC1") (pin "11") (pinfunction "I_11") (pintype "input"))
      (node (ref "IC1") (pin "12") (pinfunction "O_12") (pintype "output"))
    )
    (net (code "47") (name "Net-(IC1B-O)") (class "Default")
      (node (ref "IC1") (pin "10") (pinfunction "O_10") (pintype "output"))
      (node (ref "U1") (pin "46") (pinfunction "P0.16/EINT0/MAT0.2/CAP0.2_46") (pintype "bidirectional"))
    )
    (net (code "48") (name "Net-(IC1C-O)") (class "Default")
      (node (ref "IC1") (pin "1") (pinfunction "I_1") (pintype "input"))
      (node (ref "IC1") (pin "8") (pinfunction "O_8") (pintype "output"))
    )
    (net (code "49") (name "Net-(IC1D-O)") (class "Default")
      (node (ref "IC1") (pin "2") (pinfunction "O_2") (pintype "output"))
      (node (ref "U1") (pin "57") (pinfunction "~{RESET}_57") (pintype "input"))
    )
    (net (code "50") (name "Net-(IC2A-C1+)") (class "Default")
      (node (ref "C22") (pin "1") (pinfunction "1_1") (pintype "passive"))
      (node (ref "IC2") (pin "1") (pinfunction "C1+_1") (pintype "bidirectional"))
    )
    (net (code "51") (name "Net-(IC2A-C1-)") (class "Default")
      (node (ref "C22") (pin "2") (pinfunction "2_2") (pintype "passive"))
      (node (ref "IC2") (pin "3") (pinfunction "C1-_3") (pintype "bidirectional"))
    )
    (net (code "52") (name "Net-(IC2A-C2+)") (class "Default")
      (node (ref "C23") (pin "1") (pinfunction "1_1") (pintype "passive"))
      (node (ref "IC2") (pin "4") (pinfunction "C2+_4") (pintype "bidirectional"))
    )
    (net (code "53") (name "Net-(IC2A-C2-)") (class "Default")
      (node (ref "C23") (pin "2") (pinfunction "2_2") (pintype "passive"))
      (node (ref "IC2") (pin "5") (pinfunction "C2-_5") (pintype "bidirectional"))
    )
    (net (code "54") (name "Net-(IC2A-R1IN)") (class "Default")
      (node (ref "IC2") (pin "13") (pinfunction "R1IN_13") (pintype "input"))
      (node (ref "X7") (pin "3") (pinfunction "F_3") (pintype "passive"))
    )
    (net (code "55") (name "Net-(IC2A-T1OUT)") (class "Default")
      (node (ref "IC2") (pin "14") (pinfunction "T1OUT_14") (pintype "output"))
      (node (ref "X7") (pin "2") (pinfunction "F_2") (pintype "passive"))
    )
    (net (code "56") (name "Net-(IC2A-V+)") (class "Default")
      (node (ref "C25") (pin "2") (pinfunction "2_2") (pintype "passive"))
      (node (ref "IC2") (pin "2") (pinfunction "V+_2") (pintype "bidirectional"))
    )
    (net (code "57") (name "Net-(IC2A-V-)") (class "Default")
      (node (ref "C26") (pin "1") (pinfunction "1_1") (pintype "passive"))
      (node (ref "IC2") (pin "6") (pinfunction "V-_6") (pintype "bidirectional"))
    )
    (net (code "58") (name "Net-(JP1-Pad17)") (class "Default")
      (node (ref "JP1") (pin "17") (pinfunction "17_17") (pintype "passive"))
      (node (ref "R8") (pin "2") (pinfunction "2_2") (pintype "passive"))
    )
    (net (code "59") (name "Net-(JP1-Pad19)") (class "Default")
      (node (ref "JP1") (pin "19") (pinfunction "19_19") (pintype "passive"))
      (node (ref "R9") (pin "2") (pinfunction "2_2") (pintype "passive"))
    )
    (net (code "60") (name "Net-(PWS1-+OUT)") (class "Default")
      (node (ref "J1") (pin "3") (pinfunction "3_3") (pintype "passive"))
      (node (ref "PWS1") (pin "13") (pinfunction "+OUT_13") (pintype "output"))
    )
    (net (code "61") (name "Net-(R16-Pad1)") (class "Default")
      (node (ref "R16") (pin "1") (pinfunction "1_1") (pintype "passive"))
      (node (ref "X6") (pin "2") (pinfunction "2_2") (pintype "input"))
    )
    (net (code "62") (name "Net-(R17-Pad1)") (class "Default")
      (node (ref "R17") (pin "1") (pinfunction "1_1") (pintype "passive"))
      (node (ref "X6") (pin "3") (pinfunction "3_3") (pintype "input"))
    )
    (net (code "63") (name "Net-(U1-VBAT)") (class "Default")
      (node (ref "C6") (pin "1") (pinfunction "1_1") (pintype "passive"))
      (node (ref "U1") (pin "49") (pinfunction "VBAT_49") (pintype "power_in"))
    )
    (net (code "64") (name "Net-(U1-XTAL1)") (class "Default")
      (node (ref "C7") (pin "1") (pinfunction "1_1") (pintype "passive"))
      (node (ref "Q2") (pin "1") (pinfunction "1_1") (pintype "passive"))
      (node (ref "U1") (pin "62") (pinfunction "XTAL1_62") (pintype "input"))
    )
    (net (code "65") (name "Net-(U1-XTAL2)") (class "Default")
      (node (ref "C8") (pin "1") (pinfunction "1_1") (pintype "passive"))
      (node (ref "Q2") (pin "2") (pinfunction "2_2") (pintype "passive"))
      (node (ref "U1") (pin "61") (pinfunction "XTAL2_61") (pintype "output"))
    )
    (net (code "66") (name "Net-(U2-3V3OUT)") (class "Default")
      (node (ref "C1") (pin "1") (pinfunction "1_1") (pintype "passive"))
      (node (ref "U2") (pin "6") (pinfunction "3V3OUT_6") (pintype "output"))
    )
    (net (code "67") (name "Net-(U2-AVCC)") (class "Default")
      (node (ref "C2") (pin "1") (pinfunction "1_1") (pintype "passive"))
      (node (ref "R1") (pin "1") (pinfunction "1_1") (pintype "passive"))
      (node (ref "U2") (pin "30") (pinfunction "AVCC_30") (pintype "power_in"))
    )
    (net (code "68") (name "Net-(U2-EECS)") (class "Default")
      (node (ref "U2") (pin "32") (pinfunction "EECS_32") (pintype "bidirectional"))
      (node (ref "U3") (pin "1") (pinfunction "CS_1") (pintype "input"))
    )
    (net (code "69") (name "Net-(U2-EEDATA)") (class "Default")
      (node (ref "R19") (pin "2") (pinfunction "2_2") (pintype "passive"))
      (node (ref "U2") (pin "2") (pinfunction "EEDATA_2") (pintype "bidirectional"))
      (node (ref "U3") (pin "3") (pinfunction "DIN_3") (pintype "input"))
    )
    (net (code "70") (name "Net-(U2-EESK)") (class "Default")
      (node (ref "U2") (pin "1") (pinfunction "EESK_1") (pintype "output"))
      (node (ref "U3") (pin "2") (pinfunction "SCLK_2") (pintype "input"))
    )
    (net (code "71") (name "Net-(U2-RSTOUT#)") (class "Default")
      (node (ref "R18") (pin "2") (pinfunction "2_2") (pintype "passive"))
      (node (ref "U2") (pin "5") (pinfunction "RSTOUT#_5") (pintype "output"))
    )
    (net (code "72") (name "Net-(U2-USBDM)") (class "Default")
      (node (ref "R16") (pin "2") (pinfunction "2_2") (pintype "passive"))
      (node (ref "U2") (pin "8") (pinfunction "USBDM_8") (pintype "bidirectional"))
    )
    (net (code "73") (name "Net-(U2-USBDP)") (class "Default")
      (node (ref "R17") (pin "2") (pinfunction "2_2") (pintype "passive"))
      (node (ref "R18") (pin "1") (pinfunction "1_1") (pintype "passive"))
      (node (ref "U2") (pin "7") (pinfunction "USBDP_7") (pintype "bidirectional"))
    )
    (net (code "74") (name "Net-(U2-XTIN)") (class "Default")
      (node (ref "Q1") (pin "1") (pinfunction "1_1") (pintype "passive"))
      (node (ref "U2") (pin "27") (pinfunction "XTIN_27") (pintype "input"))
    )
    (net (code "75") (name "Net-(U2-XTOUT)") (class "Default")
      (node (ref "Q1") (pin "2") (pinfunction "2_2") (pintype "passive"))
      (node (ref "U2") (pin "28") (pinfunction "XTOUT_28") (pintype "output"))
    )
    (net (code "76") (name "Net-(U3-DOUT)") (class "Default")
      (node (ref "R19") (pin "1") (pinfunction "1_1") (pintype "passive"))
      (node (ref "R20") (pin "1") (pinfunction "1_1") (pintype "passive"))
      (node (ref "U3") (pin "4") (pinfunction "DOUT_4") (pintype "output"))
    )
    (net (code "77") (name "Net-(X1A-S)") (class "Default")
      (node (ref "C20") (pin "1") (pinfunction "1_1") (pintype "passive"))
      (node (ref "PWS1") (pin "23") (pinfunction "+IN_23") (pintype "input"))
      (node (ref "PWS1") (pin "24") (pinfunction "+IN_24") (pintype "input"))
      (node (ref "X1") (pin "1") (pinfunction "S_1") (pintype "passive"))
    )
    (net (code "78") (name "Net-(X6B-S1)") (class "Default")
      (node (ref "C27") (pin "1") (pinfunction "1_1") (pintype "passive"))
      (node (ref "R21") (pin "1") (pinfunction "1_1") (pintype "passive"))
      (node (ref "X6") (pin "M1") (pinfunction "S1_M1") (pintype "passive"))
      (node (ref "X6") (pin "M2") (pinfunction "S2_M2") (pintype "passive"))
      (node (ref "X6") (pin "M3") (pinfunction "S3_M3") (pintype "passive"))
      (node (ref "X6") (pin "M4") (pinfunction "S4_M4") (pintype "passive"))
    )
    (net (code "79") (name "unconnected-(CF1-2-Pad2@2)") (class "Default")
      (node (ref "CF1") (pin "2@2") (pinfunction "2_2@2") (pintype "passive"))
    )
    (net (code "80") (name "unconnected-(H1-MOUNT-PadB3,3)") (class "Default")
      (node (ref "H1") (pin "B3,3") (pinfunction "MOUNT_B3,3") (pintype "passive"))
    )
    (net (code "81") (name "unconnected-(H2-MOUNT-PadB3,3)") (class "Default")
      (node (ref "H2") (pin "B3,3") (pinfunction "MOUNT_B3,3") (pintype "passive"))
    )
    (net (code "82") (name "unconnected-(H3-MOUNT-PadB3,3)") (class "Default")
      (node (ref "H3") (pin "B3,3") (pinfunction "MOUNT_B3,3") (pintype "passive"))
    )
    (net (code "83") (name "unconnected-(H4-MOUNT-PadB3,3)") (class "Default")
      (node (ref "H4") (pin "B3,3") (pinfunction "MOUNT_B3,3") (pintype "passive"))
    )
    (net (code "84") (name "unconnected-(IC2A-R2IN-Pad8)") (class "Default")
      (node (ref "IC2") (pin "8") (pinfunction "R2IN_8") (pintype "input"))
    )
    (net (code "85") (name "unconnected-(IC2A-R2OUT-Pad9)") (class "Default")
      (node (ref "IC2") (pin "9") (pinfunction "R2OUT_9") (pintype "output"))
    )
    (net (code "86") (name "unconnected-(IC2A-T2IN-Pad10)") (class "Default")
      (node (ref "IC2") (pin "10") (pinfunction "T2IN_10") (pintype "input"))
    )
    (net (code "87") (name "unconnected-(IC2A-T2OUT-Pad7)") (class "Default")
      (node (ref "IC2") (pin "7") (pinfunction "T2OUT_7") (pintype "output"))
    )
    (net (code "88") (name "unconnected-(U1-D+-Pad10)") (class "Default")
      (node (ref "U1") (pin "10") (pinfunction "D+_10") (pintype "bidirectional"))
    )
    (net (code "89") (name "unconnected-(U1-D--Pad11)") (class "Default")
      (node (ref "U1") (pin "11") (pinfunction "D-_11") (pintype "bidirectional"))
    )
    (net (code "90") (name "unconnected-(U1-P0.2{slash}SCL0{slash}CAP0.0-Pad22)") (class "Default")
      (node (ref "U1") (pin "22") (pinfunction "P0.2/SCL0/CAP0.0_22") (pintype "bidirectional"))
    )
    (net (code "91") (name "unconnected-(U1-P0.3{slash}SDA0{slash}MAT0.0{slash}EINT1-Pad26)") (class "Default")
      (node (ref "U1") (pin "26") (pinfunction "P0.3/SDA0/MAT0.0/EINT1_26") (pintype "bidirectional"))
    )
    (net (code "92") (name "unconnected-(U1-P0.17{slash}CAP1.2{slash}SCK1{slash}MAT1.2-Pad47)") (class "Default")
      (node (ref "U1") (pin "47") (pinfunction "P0.17/CAP1.2/SCK1/MAT1.2_47") (pintype "bidirectional"))
    )
    (net (code "93") (name "unconnected-(U1-P0.18{slash}CAP1.3{slash}MISO1{slash}MAT1.3-Pad53)") (class "Default")
      (node (ref "U1") (pin "53") (pinfunction "P0.18/CAP1.3/MISO1/MAT1.3_53") (pintype "bidirectional"))
    )
    (net (code "94") (name "unconnected-(U1-P0.19{slash}MAT1.2{slash}MOSI1{slash}CAP1.2-Pad54)") (class "Default")
      (node (ref "U1") (pin "54") (pinfunction "P0.19/MAT1.2/MOSI1/CAP1.2_54") (pintype "bidirectional"))
    )
    (net (code "95") (name "unconnected-(U1-P0.20{slash}MAT1.3{slash}SSEL1{slash}EINT3-Pad55)") (class "Default")
      (node (ref "U1") (pin "55") (pinfunction "P0.20/MAT1.3/SSEL1/EINT3_55") (pintype "bidirectional"))
    )
    (net (code "96") (name "unconnected-(U1-P0.22{slash}AD1.7{slash}CAP0.0{slash}MAT0.0-Pad2)") (class "Default")
      (node (ref "U1") (pin "2") (pinfunction "P0.22/AD1.7/CAP0.0/MAT0.0_2") (pintype "bidirectional"))
    )
    (net (code "97") (name "unconnected-(U1-P0.23{slash}VBUS-Pad58)") (class "Default")
      (node (ref "U1") (pin "58") (pinfunction "P0.23/VBUS_58") (pintype "bidirectional"))
    )
    (net (code "98") (name "unconnected-(U1-P0.31{slash}UP_LED{slash}CONNECT-Pad17)") (class "Default")
      (node (ref "U1") (pin "17") (pinfunction "P0.31/UP_LED/CONNECT_17") (pintype "bidirectional"))
    )
    (net (code "99") (name "unconnected-(U1-P1.24{slash}TRACECLK-Pad32)") (class "Default")
      (node (ref "U1") (pin "32") (pinfunction "P1.24/TRACECLK_32") (pintype "bidirectional"))
    )
    (net (code "100") (name "unconnected-(U1-P1.25{slash}EXTIN0-Pad28)") (class "Default")
      (node (ref "U1") (pin "28") (pinfunction "P1.25/EXTIN0_28") (pintype "bidirectional"))
    )
    (net (code "101") (name "unconnected-(U1-RTXC1-Pad3)") (class "Default")
      (node (ref "U1") (pin "3") (pinfunction "RTXC1_3") (pintype "input"))
    )
    (net (code "102") (name "unconnected-(U1-RTXC2-Pad5)") (class "Default")
      (node (ref "U1") (pin "5") (pinfunction "RTXC2_5") (pintype "output"))
    )
    (net (code "103") (name "unconnected-(U2-DCD#-Pad19)") (class "Default")
      (node (ref "U2") (pin "19") (pinfunction "DCD#_19") (pintype "input"))
    )
    (net (code "104") (name "unconnected-(U2-DSR#-Pad20)") (class "Default")
      (node (ref "U2") (pin "20") (pinfunction "DSR#_20") (pintype "input"))
    )
    (net (code "105") (name "unconnected-(U2-DTR#-Pad21)") (class "Default")
      (node (ref "U2") (pin "21") (pinfunction "DTR#_21") (pintype "output"))
    )
    (net (code "106") (name "unconnected-(U2-PWREN#-Pad15)") (class "Default")
      (node (ref "U2") (pin "15") (pinfunction "PWREN#_15") (pintype "output"))
    )
    (net (code "107") (name "unconnected-(U2-RI#-Pad18)") (class "Default")
      (node (ref "U2") (pin "18") (pinfunction "RI#_18") (pintype "input"))
    )
    (net (code "108") (name "unconnected-(U2-RXLED#-Pad11)") (class "Default")
      (node (ref "U2") (pin "11") (pinfunction "RXLED#_11") (pintype "open_collector"))
    )
    (net (code "109") (name "unconnected-(U2-SLEEP#-Pad10)") (class "Default")
      (node (ref "U2") (pin "10") (pinfunction "SLEEP#_10") (pintype "output"))
    )
    (net (code "110") (name "unconnected-(U2-TXDEN-Pad16)") (class "Default")
      (node (ref "U2") (pin "16") (pinfunction "TXDEN_16") (pintype "output"))
    )
    (net (code "111") (name "unconnected-(U2-TXLED#-Pad12)") (class "Default")
      (node (ref "U2") (pin "12") (pinfunction "TXLED#_12") (pintype "open_collector"))
    )
    (net (code "112") (name "unconnected-(X2H-S-Pad8)") (class "Default")
      (node (ref "X2") (pin "8") (pinfunction "S_8") (pintype "passive"))
    )
    (net (code "113") (name "unconnected-(X3H-S-Pad8)") (class "Default")
      (node (ref "X3") (pin "8") (pinfunction "S_8") (pintype "passive"))
    )
    (net (code "114") (name "unconnected-(X4H-S-Pad8)") (class "Default")
      (node (ref "X4") (pin "8") (pinfunction "S_8") (pintype "passive"))
    )
    (net (code "115") (name "unconnected-(X5H-S-Pad8)") (class "Default")
      (node (ref "X5") (pin "8") (pinfunction "S_8") (pintype "passive"))
    )
  )
)
